# nguon24v.net
KiCad netlist of a schematic drawn in Altium Designer
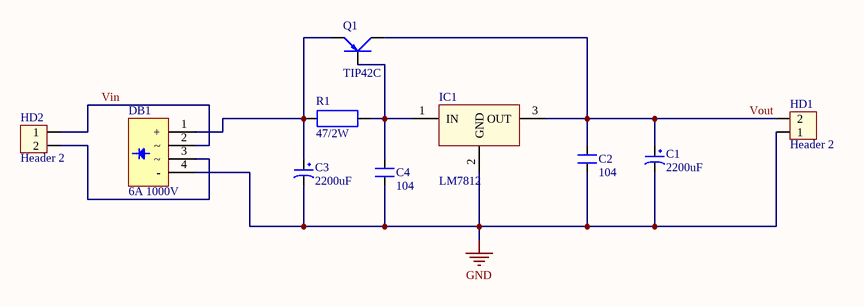
[diagram p0: nguon24v.SchDoc]

(export (version "E")
  (design (tool "Eeschema 10.0.6"))
  (components
    (comp (ref "C1")
      (value "2200uF")
      (footprint "CP1/2")
      (description "Cap P  0,1uF < 22uF , 16 - 50V")
      (libsource (lib "syhaunguyen") (part "CP1"))
    )
    (comp (ref "C2")
      (value "104")
      (footprint "CN1.5")
      (description "Cap np 682pF => 104pF")
      (libsource (lib "syhaunguyen") (part "CN1.5"))
    )
    (comp (ref "C3")
      (value "2200uF")
      (footprint "CP1/2")
      (description "Cap P  0,1uF < 22uF , 16 - 50V")
      (libsource (lib "syhaunguyen") (part "CP1"))
    )
    (comp (ref "C4")
      (value "104")
      (footprint "CN1.5")
      (description "Cap np 682pF => 104pF")
      (libsource (lib "syhaunguyen") (part "CN1.5"))
    )
    (comp (ref "DB1")
      (value "6A 1000V")
      (footprint "DIODE CAU 6A CAM")
      (description "Cắm")
      (libsource (lib "Altium_Lib_by_KhueNguyenCreator") (part "Diode CAU 6A"))
    )
    (comp (ref "HD1")
      (value "Header 2")
      (footprint "HED2")
      (description "Header 2 (Green)")
      (libsource (lib "") (part "Hed2_1"))
    )
    (comp (ref "HD2")
      (value "Header 2")
      (footprint "HED2")
      (description "Header 2 (Green)")
      (libsource (lib "syhaunguyen") (part "Hed2"))
    )
    (comp (ref "IC1")
      (value "LM7812")
      (footprint "QTO-220")
      (description "On ap +, from + 5 to + 24VDC")
      (libsource (lib "syhaunguyen") (part "LM78xx"))
    )
    (comp (ref "Q1")
      (value "TIP42C")
      (footprint "QTO-220")
      (description "PNP 2W, BCE")
      (libsource (lib "syhaunguyen") (part "TIP42C"))
    )
    (comp (ref "R1")
      (value "47/2W")
      (footprint "R2W")
      (description "Resistor 2W")
      (libsource (lib "syhaunguyen") (part "R2W"))
    )
  )
  (nets
    (net (code "1") (name "/Vin") (class "Default")
      (node (ref "DB1") (pin "2") (pinfunction "~_2") (pintype "passive"))
      (node (ref "HD2") (pin "1") (pinfunction "1_1") (pintype "passive"))
    )
    (net (code "2") (name "/Vout") (class "Default")
      (node (ref "C1") (pin "1") (pinfunction "1_1") (pintype "passive"))
      (node (ref "C2") (pin "2") (pinfunction "2_2") (pintype "passive"))
      (node (ref "HD1") (pin "2") (pinfunction "2_2") (pintype "passive"))
      (node (ref "IC1") (pin "3") (pinfunction "OUT_3") (pintype "passive"))
      (node (ref "Q1") (pin "2") (pinfunction "C_2") (pintype "passive"))
    )
    (net (code "3") (name "GND") (class "Default")
      (node (ref "C1") (pin "2") (pinfunction "2_2") (pintype "passive"))
      (node (ref "C2") (pin "1") (pinfunction "1_1") (pintype "passive"))
      (node (ref "C3") (pin "2") (pinfunction "2_2") (pintype "passive"))
      (node (ref "C4") (pin "1") (pinfunction "1_1") (pintype "passive"))
      (node (ref "DB1") (pin "4") (pinfunction "-_4") (pintype "passive"))
      (node (ref "HD1") (pin "1") (pinfunction "1_1") (pintype "passive"))
      (node (ref "IC1") (pin "2") (pinfunction "GND_2") (pintype "passive"))
    )
    (net (code "4") (name "Net-(DB1-+)") (class "Default")
      (node (ref "C3") (pin "1") (pinfunction "1_1") (pintype "passive"))
      (node (ref "DB1") (pin "1") (pinfunction "+_1") (pintype "passive"))
      (node (ref "Q1") (pin "3") (pinfunction "E_3") (pintype "passive"))
      (node (ref "R1") (pin "1") (pinfunction "1_1") (pintype "passive"))
    )
    (net (code "5") (name "Net-(DB1-~-Pad3)") (class "Default")
      (node (ref "DB1") (pin "3") (pinfunction "~_3") (pintype "passive"))
      (node (ref "HD2") (pin "2") (pinfunction "2_2") (pintype "passive"))
    )
    (net (code "6") (name "Net-(IC1-IN)") (class "Default")
      (node (ref "C4") (pin "2") (pinfunction "2_2") (pintype "passive"))
      (node (ref "IC1") (pin "1") (pinfunction "IN_1") (pintype "passive"))
      (node (ref "Q1") (pin "1") (pinfunction "B_1") (pintype "passive"))
      (node (ref "R1") (pin "2") (pinfunction "2_2") (pintype "passive"))
    )
  )
)
